# BME280_Breakout.net
KiCad netlist of a schematic drawn in EAGLE
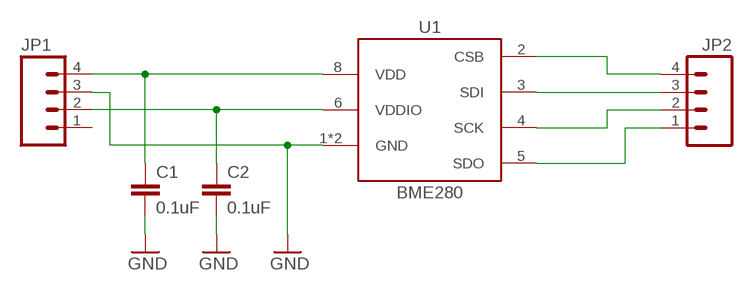
[diagram p0: schematic, sheet 1]

(export (version "E")
  (design (tool "Eeschema 10.0.6"))
  (components
    (comp (ref "C1")
      (value "0.1uF")
      (footprint "eagle-import:0402-CAP")
      (libsource (lib "eagle-import") (part "0.1UF-16V(+-10%)(0402)"))
    )
    (comp (ref "C2")
      (value "0.1uF")
      (footprint "eagle-import:0402-CAP")
      (libsource (lib "eagle-import") (part "0.1UF-16V(+-10%)(0402)"))
    )
    (comp (ref "JP1")
      (value "M04NO_SILK_ALL_ROUND")
      (footprint "eagle-import:1X04_NO_SILK_ALL_ROUND")
      (libsource (lib "eagle-import") (part "M04NO_SILK_ALL_ROUND"))
    )
    (comp (ref "JP2")
      (value "M04NO_SILK_ALL_ROUND")
      (footprint "eagle-import:1X04_NO_SILK_ALL_ROUND")
      (libsource (lib "eagle-import") (part "M04NO_SILK_ALL_ROUND"))
    )
    (comp (ref "U1")
      (value "BME280")
      (footprint "eagle-import:BME280")
      (libsource (lib "eagle-import") (part "BME280"))
    )
  )
  (nets
    (net (code "1") (name "GND") (class "Default")
      (node (ref "C1") (pin "2") (pinfunction "2_2") (pintype "passive"))
      (node (ref "C2") (pin "2") (pinfunction "2_2") (pintype "passive"))
      (node (ref "JP1") (pin "3") (pinfunction "3_3") (pintype "passive"))
      (node (ref "U1") (pin "1") (pinfunction "GND_1") (pintype "passive"))
      (node (ref "U1") (pin "7") (pinfunction "GND_7") (pintype "passive"))
    )
    (net (code "2") (name "Net-(U1-CSB)") (class "Default")
      (node (ref "JP2") (pin "4") (pinfunction "4_4") (pintype "passive"))
      (node (ref "U1") (pin "2") (pinfunction "CSB_2") (pintype "input"))
    )
    (net (code "3") (name "Net-(U1-SCK)") (class "Default")
      (node (ref "JP2") (pin "2") (pinfunction "2_2") (pintype "passive"))
      (node (ref "U1") (pin "4") (pinfunction "SCK_4") (pintype "input"))
    )
    (net (code "4") (name "Net-(U1-SDI)") (class "Default")
      (node (ref "JP2") (pin "3") (pinfunction "3_3") (pintype "passive"))
      (node (ref "U1") (pin "3") (pinfunction "SDI_3") (pintype "bidirectional"))
    )
    (net (code "5") (name "Net-(U1-SDO)") (class "Default")
      (node (ref "JP2") (pin "1") (pinfunction "1_1") (pintype "passive"))
      (node (ref "U1") (pin "5") (pinfunction "SDO_5") (pintype "bidirectional"))
    )
    (net (code "6") (name "Net-(U1-VDD)") (class "Default")
      (node (ref "C1") (pin "1") (pinfunction "1_1") (pintype "passive"))
      (node (ref "JP1") (pin "4") (pinfunction "4_4") (pintype "passive"))
      (node (ref "U1") (pin "8") (pinfunction "VDD_8") (pintype "power_in"))
    )
    (net (code "7") (name "Net-(U1-VDDIO)") (class "Default")
      (node (ref "C2") (pin "1") (pinfunction "1_1") (pintype "passive"))
      (node (ref "JP1") (pin "2") (pinfunction "2_2") (pintype "passive"))
      (node (ref "U1") (pin "6") (pinfunction "VDDIO_6") (pintype "power_in"))
    )
    (net (code "8") (name "unconnected-(JP1-Pad1)") (class "Default")
      (node (ref "JP1") (pin "1") (pinfunction "1_1") (pintype "passive"))
    )
  )
)
